# Divider.net
KiCad netlist of a schematic drawn in Altium Designer
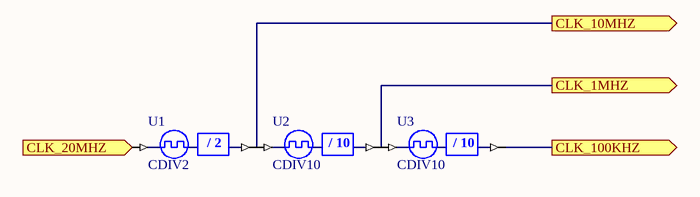
[diagram p0: Divider.schdoc]

(export (version "E")
  (design (tool "Eeschema 10.0.6"))
  (components
    (comp (ref "U1")
      (value "CDIV2")
      (description "Clock Divider by 2")
      (fields (field (name "PUBLISHER") "Altium Limited"))
      (libsource (lib "FPGA Generic") (part "CDIV2"))
    )
    (comp (ref "U2")
      (value "CDIV10")
      (description "Clock Divider by 10")
      (fields (field (name "PUBLISHER") "Altium Limited"))
      (libsource (lib "FPGA Generic") (part "CDIV10"))
    )
    (comp (ref "U3")
      (value "CDIV10")
      (description "Clock Divider by 10")
      (fields (field (name "PUBLISHER") "Altium Limited"))
      (libsource (lib "FPGA Generic") (part "CDIV10"))
    )
  )
  (nets
    (net (code "1") (name "/CLK_1MHZ") (class "Default")
      (node (ref "U2") (pin "CLKDV") (pinfunction "CLKDV_CLKDV") (pintype "output"))
      (node (ref "U3") (pin "CLKIN") (pinfunction "CLKIN_CLKIN") (pintype "input"))
    )
    (net (code "2") (name "/CLK_10MHZ") (class "Default")
      (node (ref "U1") (pin "CLKDV") (pinfunction "CLKDV_CLKDV") (pintype "output"))
      (node (ref "U2") (pin "CLKIN") (pinfunction "CLKIN_CLKIN") (pintype "input"))
    )
    (net (code "3") (name "/CLK_20MHZ") (class "Default")
      (node (ref "U1") (pin "CLKIN") (pinfunction "CLKIN_CLKIN") (pintype "input"))
    )
    (net (code "4") (name "/CLK_100KHZ") (class "Default")
      (node (ref "U3") (pin "CLKDV") (pinfunction "CLKDV_CLKDV") (pintype "output"))
    )
  )
)
